# KeepUntil-v1_0_0.net
KiCad netlist of a schematic drawn in EAGLE
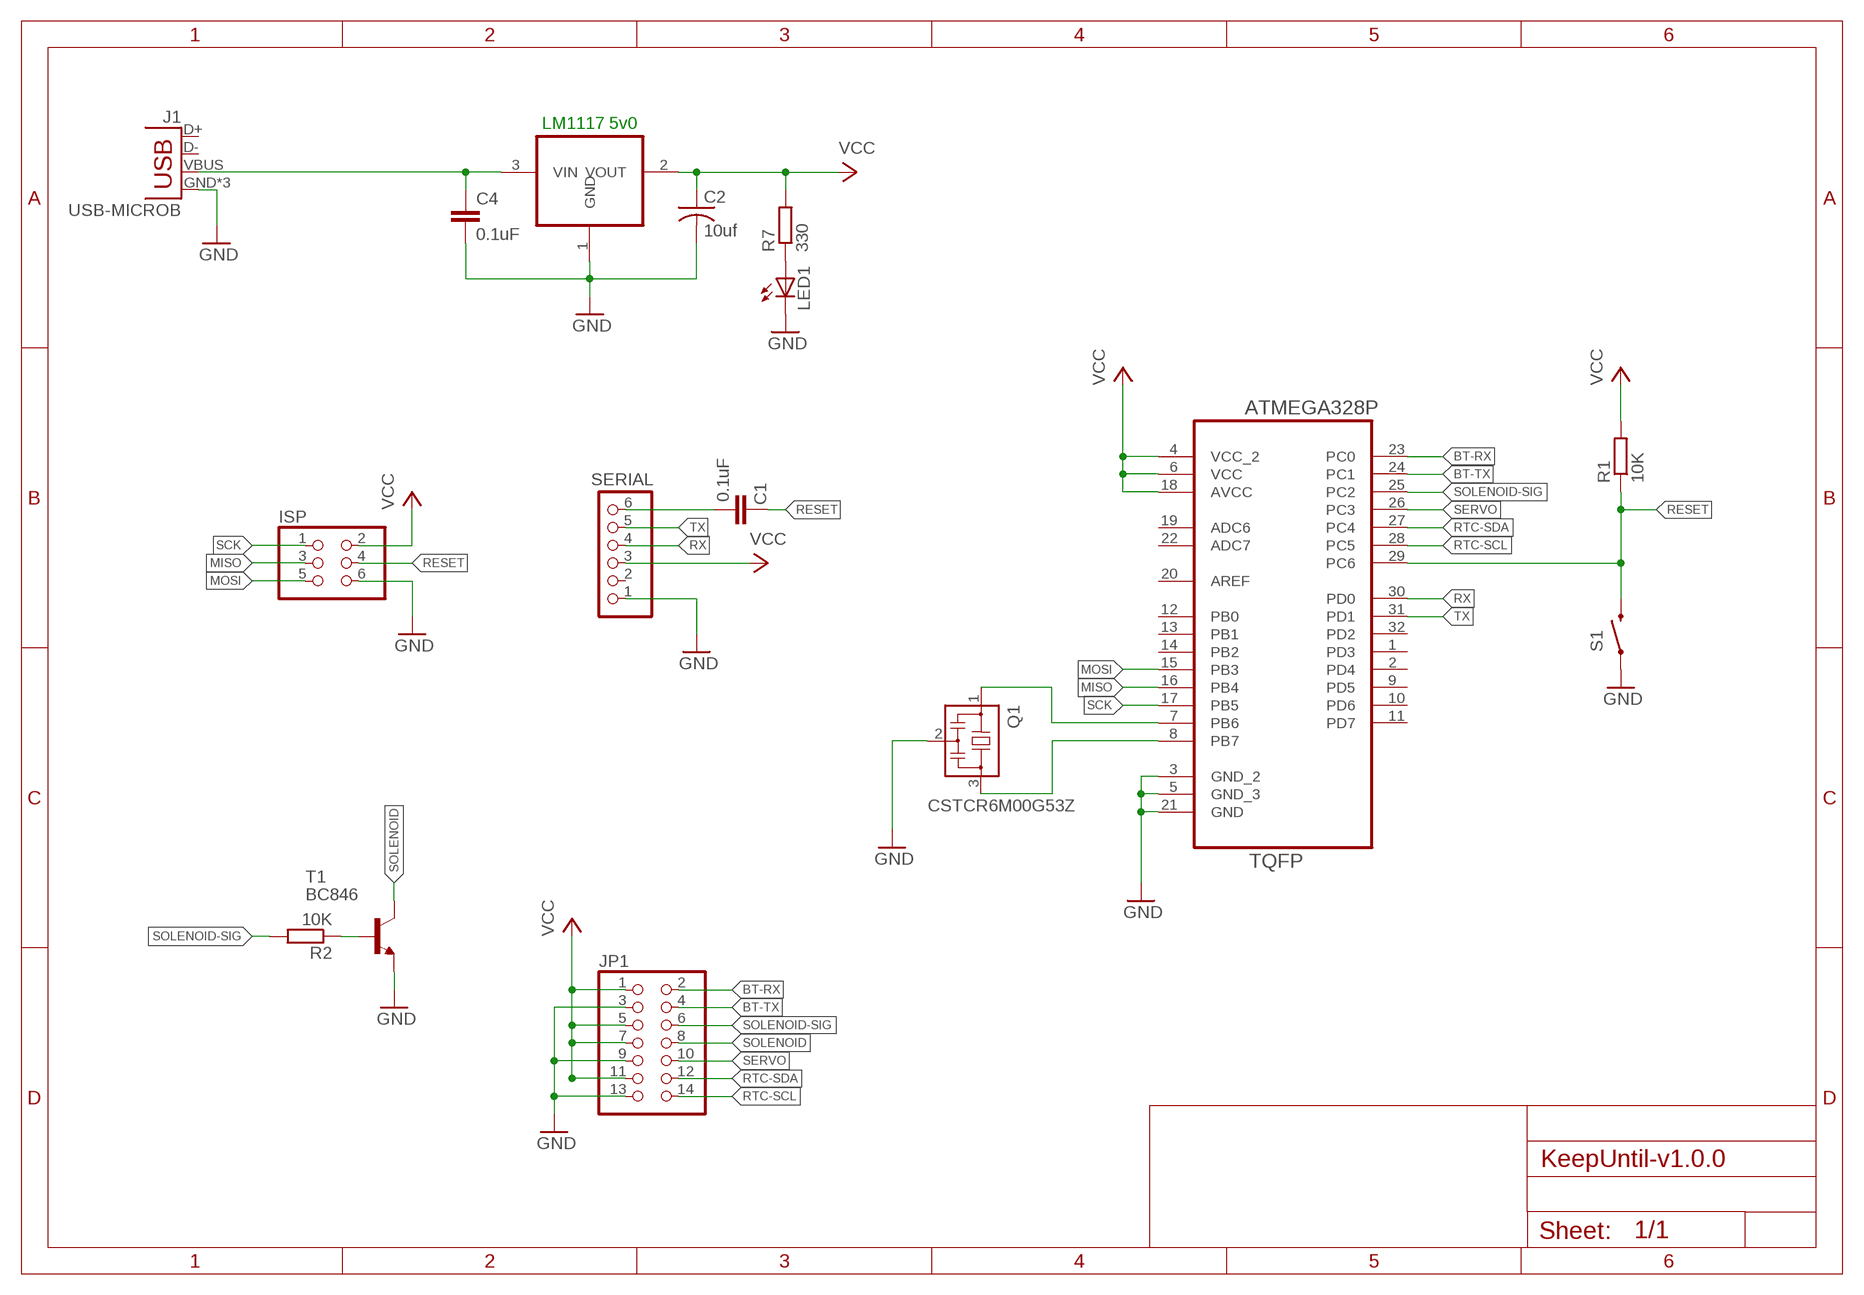
[diagram p0: schematic, sheet 1]

(export (version "E")
  (design (tool "Eeschema 10.0.6"))
  (components
    (comp (ref "C1")
      (value "0.1uF")
      (footprint "eagle-import:C0805")
      (libsource (lib "eagle-import") (part "C-EUC0805"))
    )
    (comp (ref "C2")
      (value "10uf")
      (footprint "eagle-import:C1206")
      (libsource (lib "eagle-import") (part "C-USC1206"))
    )
    (comp (ref "C4")
      (value "0.1uF")
      (footprint "eagle-import:C0805")
      (libsource (lib "eagle-import") (part "C-EUC0805"))
    )
    (comp (ref "IC2")
      (value "REG1117")
      (footprint "eagle-import:SOT223")
      (fields (field (name "MPN") "LM1117 3v3"))
      (libsource (lib "eagle-import") (part "REG1117"))
    )
    (comp (ref "ISP")
      (value "PINHD-2X3")
      (footprint "eagle-import:2X03")
      (libsource (lib "eagle-import") (part "PINHD-2X3"))
    )
    (comp (ref "J1")
      (value "USB-MICROB")
      (footprint "eagle-import:USB-MICROB")
      (libsource (lib "eagle-import") (part "USB-MICROB"))
    )
    (comp (ref "JP1")
      (value "PINHD-2X7")
      (footprint "eagle-import:2X07")
      (libsource (lib "eagle-import") (part "PINHD-2X7"))
    )
    (comp (ref "LED1")
      (value "LEDSMT1206")
      (footprint "eagle-import:1206")
      (libsource (lib "eagle-import") (part "LEDSMT1206"))
    )
    (comp (ref "Q1")
      (value "CSTCR6M00G53Z")
      (footprint "eagle-import:CSTCR6M")
      (fields (field (name "MPN") "CSTCR6M00G53-R0"))
      (libsource (lib "eagle-import") (part "CSTCR6M00G53Z"))
    )
    (comp (ref "R1")
      (value "10K")
      (footprint "eagle-import:R0805")
      (libsource (lib "eagle-import") (part "R-EU_R0805"))
    )
    (comp (ref "R2")
      (value "10K")
      (footprint "eagle-import:R0805")
      (libsource (lib "eagle-import") (part "R-EU_R0805"))
    )
    (comp (ref "R7")
      (value "330")
      (footprint "eagle-import:R0805")
      (libsource (lib "eagle-import") (part "R-EU_R0805"))
    )
    (comp (ref "S1")
      (value "SWITCH-MOMENTARY-2SMD-1101NE")
      (footprint "eagle-import:TACTILE-SWITCH-1101NE")
      (libsource (lib "eagle-import") (part "SWITCH-MOMENTARY-2SMD-1101NE"))
    )
    (comp (ref "SERIAL")
      (value "PINHD-1X6")
      (footprint "eagle-import:1X06")
      (libsource (lib "eagle-import") (part "PINHD-1X6"))
    )
    (comp (ref "T1")
      (value "BC846")
      (footprint "eagle-import:SOT23")
      (libsource (lib "eagle-import") (part "BC846"))
    )
    (comp (ref "U1")
      (value "ATMEGA328P-AU")
      (footprint "eagle-import:QFP80P900X900X120-32N")
      (libsource (lib "eagle-import") (part "ATMEGA328P-AU"))
    )
  )
  (nets
    (net (code "1") (name "BT-RX") (class "Default")
      (node (ref "JP1") (pin "2") (pinfunction "2_2") (pintype "passive"))
      (node (ref "U1") (pin "23") (pinfunction "PC0_23") (pintype "bidirectional"))
    )
    (net (code "2") (name "BT-TX") (class "Default")
      (node (ref "JP1") (pin "4") (pinfunction "4_4") (pintype "passive"))
      (node (ref "U1") (pin "24") (pinfunction "PC1_24") (pintype "bidirectional"))
    )
    (net (code "3") (name "GND") (class "Default")
      (node (ref "C2") (pin "2") (pinfunction "2_2") (pintype "passive"))
      (node (ref "C4") (pin "2") (pinfunction "2_2") (pintype "passive"))
      (node (ref "IC2") (pin "1") (pinfunction "GND_1") (pintype "power_in"))
      (node (ref "ISP") (pin "6") (pinfunction "6_6") (pintype "passive"))
      (node (ref "J1") (pin "GND") (pinfunction "GND_GND") (pintype "bidirectional"))
      (node (ref "J1") (pin "MT1") (pinfunction "GND_MT1") (pintype "bidirectional"))
      (node (ref "J1") (pin "MT2") (pinfunction "GND_MT2") (pintype "bidirectional"))
      (node (ref "JP1") (pin "13") (pinfunction "13_13") (pintype "passive"))
      (node (ref "JP1") (pin "3") (pinfunction "3_3") (pintype "passive"))
      (node (ref "JP1") (pin "9") (pinfunction "9_9") (pintype "passive"))
      (node (ref "LED1") (pin "C") (pinfunction "C_C") (pintype "passive"))
      (node (ref "Q1") (pin "2") (pinfunction "2_2") (pintype "passive"))
      (node (ref "S1") (pin "1") (pinfunction "1_1") (pintype "passive"))
      (node (ref "SERIAL") (pin "1") (pinfunction "1_1") (pintype "passive"))
      (node (ref "T1") (pin "2") (pinfunction "E_2") (pintype "passive"))
      (node (ref "U1") (pin "21") (pinfunction "GND_21") (pintype "passive"))
      (node (ref "U1") (pin "3") (pinfunction "GND_2_3") (pintype "passive"))
      (node (ref "U1") (pin "5") (pinfunction "GND_3_5") (pintype "passive"))
    )
    (net (code "4") (name "MISO") (class "Default")
      (node (ref "ISP") (pin "3") (pinfunction "3_3") (pintype "passive"))
      (node (ref "U1") (pin "16") (pinfunction "PB4_16") (pintype "bidirectional"))
    )
    (net (code "5") (name "MOSI") (class "Default")
      (node (ref "ISP") (pin "5") (pinfunction "5_5") (pintype "passive"))
      (node (ref "U1") (pin "15") (pinfunction "PB3_15") (pintype "bidirectional"))
    )
    (net (code "6") (name "Net-(C1-Pad2)") (class "Default")
      (node (ref "C1") (pin "2") (pinfunction "2_2") (pintype "passive"))
      (node (ref "SERIAL") (pin "6") (pinfunction "6_6") (pintype "passive"))
    )
    (net (code "7") (name "Net-(IC2-VIN)") (class "Default")
      (node (ref "C4") (pin "1") (pinfunction "1_1") (pintype "passive"))
      (node (ref "IC2") (pin "3") (pinfunction "VIN_3") (pintype "input"))
      (node (ref "J1") (pin "VBUS") (pinfunction "VBUS_VBUS") (pintype "bidirectional"))
    )
    (net (code "8") (name "Net-(LED1-PadA)") (class "Default")
      (node (ref "LED1") (pin "A") (pinfunction "A_A") (pintype "passive"))
      (node (ref "R7") (pin "1") (pinfunction "1_1") (pintype "passive"))
    )
    (net (code "9") (name "Net-(T1-B)") (class "Default")
      (node (ref "R2") (pin "1") (pinfunction "1_1") (pintype "passive"))
      (node (ref "T1") (pin "1") (pinfunction "B_1") (pintype "passive"))
    )
    (net (code "10") (name "Net-(U1-PB6)") (class "Default")
      (node (ref "Q1") (pin "1") (pinfunction "1_1") (pintype "passive"))
      (node (ref "U1") (pin "7") (pinfunction "PB6_7") (pintype "bidirectional"))
    )
    (net (code "11") (name "Net-(U1-PB7)") (class "Default")
      (node (ref "Q1") (pin "3") (pinfunction "3_3") (pintype "passive"))
      (node (ref "U1") (pin "8") (pinfunction "PB7_8") (pintype "bidirectional"))
    )
    (net (code "12") (name "RESET") (class "Default")
      (node (ref "C1") (pin "1") (pinfunction "1_1") (pintype "passive"))
      (node (ref "ISP") (pin "4") (pinfunction "4_4") (pintype "passive"))
      (node (ref "R1") (pin "1") (pinfunction "1_1") (pintype "passive"))
      (node (ref "S1") (pin "2") (pinfunction "2_2") (pintype "passive"))
      (node (ref "U1") (pin "29") (pinfunction "PC6_29") (pintype "bidirectional"))
    )
    (net (code "13") (name "RTC-SCL") (class "Default")
      (node (ref "JP1") (pin "14") (pinfunction "14_14") (pintype "passive"))
      (node (ref "U1") (pin "28") (pinfunction "PC5_28") (pintype "bidirectional"))
    )
    (net (code "14") (name "RTC-SDA") (class "Default")
      (node (ref "JP1") (pin "12") (pinfunction "12_12") (pintype "passive"))
      (node (ref "U1") (pin "27") (pinfunction "PC4_27") (pintype "bidirectional"))
    )
    (net (code "15") (name "RX") (class "Default")
      (node (ref "SERIAL") (pin "4") (pinfunction "4_4") (pintype "passive"))
      (node (ref "U1") (pin "30") (pinfunction "PD0_30") (pintype "bidirectional"))
    )
    (net (code "16") (name "SCK") (class "Default")
      (node (ref "ISP") (pin "1") (pinfunction "1_1") (pintype "passive"))
      (node (ref "U1") (pin "17") (pinfunction "PB5_17") (pintype "bidirectional"))
    )
    (net (code "17") (name "SERVO") (class "Default")
      (node (ref "JP1") (pin "10") (pinfunction "10_10") (pintype "passive"))
      (node (ref "U1") (pin "26") (pinfunction "PC3_26") (pintype "bidirectional"))
    )
    (net (code "18") (name "SOLENOID") (class "Default")
      (node (ref "JP1") (pin "8") (pinfunction "8_8") (pintype "passive"))
      (node (ref "T1") (pin "3") (pinfunction "C_3") (pintype "passive"))
    )
    (net (code "19") (name "SOLENOID-SIG") (class "Default")
      (node (ref "JP1") (pin "6") (pinfunction "6_6") (pintype "passive"))
      (node (ref "R2") (pin "2") (pinfunction "2_2") (pintype "passive"))
      (node (ref "U1") (pin "25") (pinfunction "PC2_25") (pintype "bidirectional"))
    )
    (net (code "20") (name "TX") (class "Default")
      (node (ref "SERIAL") (pin "5") (pinfunction "5_5") (pintype "passive"))
      (node (ref "U1") (pin "31") (pinfunction "PD1_31") (pintype "bidirectional"))
    )
    (net (code "21") (name "VCC") (class "Default")
      (node (ref "C2") (pin "1") (pinfunction "1_1") (pintype "passive"))
      (node (ref "IC2") (pin "2") (pinfunction "VOUT_2") (pintype "power_in"))
      (node (ref "ISP") (pin "2") (pinfunction "2_2") (pintype "passive"))
      (node (ref "JP1") (pin "1") (pinfunction "1_1") (pintype "passive"))
      (node (ref "JP1") (pin "11") (pinfunction "11_11") (pintype "passive"))
      (node (ref "JP1") (pin "5") (pinfunction "5_5") (pintype "passive"))
      (node (ref "JP1") (pin "7") (pinfunction "7_7") (pintype "passive"))
      (node (ref "R1") (pin "2") (pinfunction "2_2") (pintype "passive"))
      (node (ref "R7") (pin "2") (pinfunction "2_2") (pintype "passive"))
      (node (ref "SERIAL") (pin "3") (pinfunction "3_3") (pintype "passive"))
      (node (ref "U1") (pin "18") (pinfunction "AVCC_18") (pintype "power_in"))
      (node (ref "U1") (pin "4") (pinfunction "VCC_2_4") (pintype "power_in"))
      (node (ref "U1") (pin "6") (pinfunction "VCC_6") (pintype "power_in"))
    )
    (net (code "22") (name "unconnected-(J1-PadD+)") (class "Default")
      (node (ref "J1") (pin "D+") (pinfunction "D+_D+") (pintype "bidirectional"))
    )
    (net (code "23") (name "unconnected-(J1-PadD-)") (class "Default")
      (node (ref "J1") (pin "D-") (pinfunction "D-_D-") (pintype "bidirectional"))
    )
    (net (code "24") (name "unconnected-(SERIAL-Pad2)") (class "Default")
      (node (ref "SERIAL") (pin "2") (pinfunction "2_2") (pintype "passive"))
    )
    (net (code "25") (name "unconnected-(U1-ADC6-Pad19)") (class "Default")
      (node (ref "U1") (pin "19") (pinfunction "ADC6_19") (pintype "input"))
    )
    (net (code "26") (name "unconnected-(U1-ADC7-Pad22)") (class "Default")
      (node (ref "U1") (pin "22") (pinfunction "ADC7_22") (pintype "input"))
    )
    (net (code "27") (name "unconnected-(U1-AREF-Pad20)") (class "Default")
      (node (ref "U1") (pin "20") (pinfunction "AREF_20") (pintype "input"))
    )
    (net (code "28") (name "unconnected-(U1-PB0-Pad12)") (class "Default")
      (node (ref "U1") (pin "12") (pinfunction "PB0_12") (pintype "bidirectional"))
    )
    (net (code "29") (name "unconnected-(U1-PB1-Pad13)") (class "Default")
      (node (ref "U1") (pin "13") (pinfunction "PB1_13") (pintype "bidirectional"))
    )
    (net (code "30") (name "unconnected-(U1-PB2-Pad14)") (class "Default")
      (node (ref "U1") (pin "14") (pinfunction "PB2_14") (pintype "bidirectional"))
    )
    (net (code "31") (name "unconnected-(U1-PD2-Pad32)") (class "Default")
      (node (ref "U1") (pin "32") (pinfunction "PD2_32") (pintype "bidirectional"))
    )
    (net (code "32") (name "unconnected-(U1-PD3-Pad1)") (class "Default")
      (node (ref "U1") (pin "1") (pinfunction "PD3_1") (pintype "bidirectional"))
    )
    (net (code "33") (name "unconnected-(U1-PD4-Pad2)") (class "Default")
      (node (ref "U1") (pin "2") (pinfunction "PD4_2") (pintype "bidirectional"))
    )
    (net (code "34") (name "unconnected-(U1-PD5-Pad9)") (class "Default")
      (node (ref "U1") (pin "9") (pinfunction "PD5_9") (pintype "bidirectional"))
    )
    (net (code "35") (name "unconnected-(U1-PD6-Pad10)") (class "Default")
      (node (ref "U1") (pin "10") (pinfunction "PD6_10") (pintype "bidirectional"))
    )
    (net (code "36") (name "unconnected-(U1-PD7-Pad11)") (class "Default")
      (node (ref "U1") (pin "11") (pinfunction "PD7_11") (pintype "bidirectional"))
    )
  )
)
